# design_bci.net
KiCad netlist of a schematic drawn in EAGLE
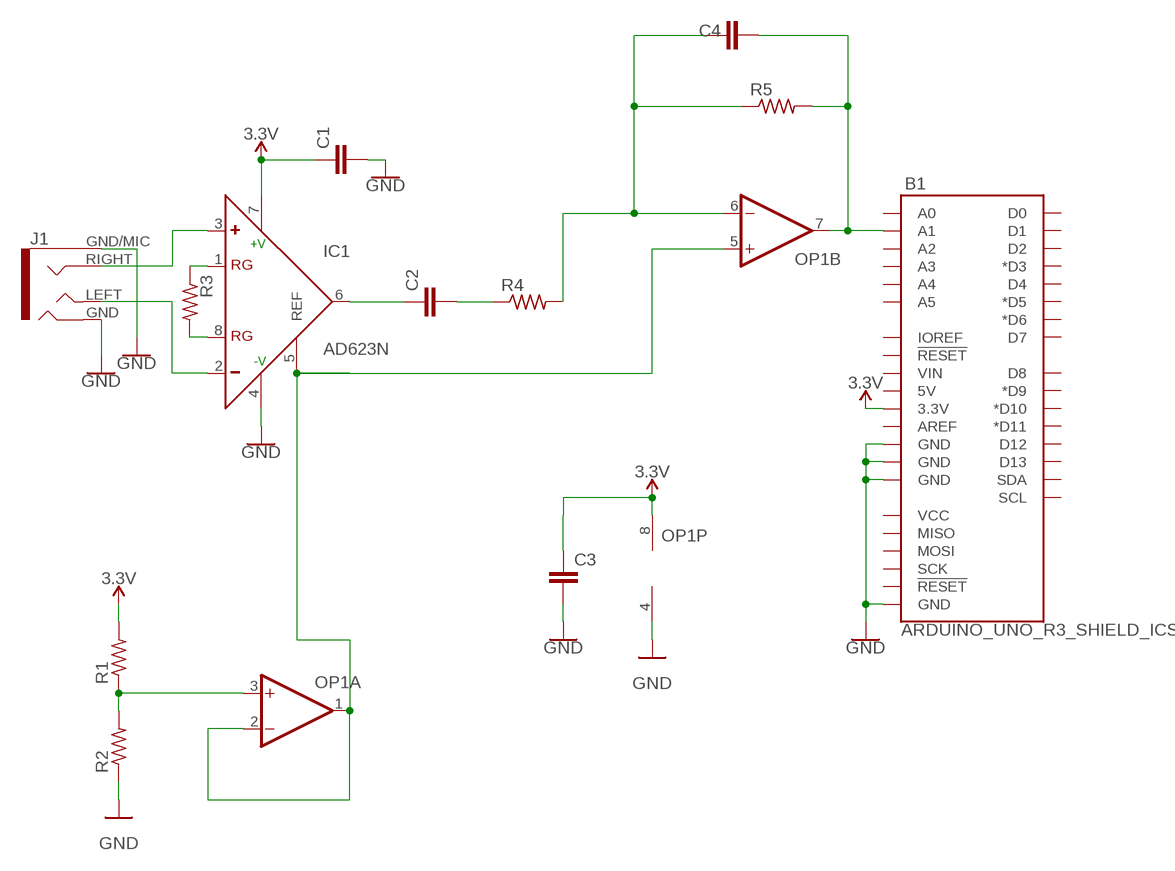
[diagram p0: schematic, sheet 1]

(export (version "E")
  (design (tool "Eeschema 10.0.6"))
  (components
    (comp (ref "B1")
      (value "ARDUINO_UNO_R3_SHIELD_ICSP")
      (footprint "eagle-import:UNO_R3_SHIELD_ICSP")
      (libsource (lib "eagle-import") (part "ARDUINO_UNO_R3_SHIELD_ICSP"))
    )
    (comp (ref "C1")
      (value "CAPACITOR0603")
      (footprint "eagle-import:C0603")
      (libsource (lib "eagle-import") (part "CAPACITOR0603"))
    )
    (comp (ref "C2")
      (value "CAPACITOR0603")
      (footprint "eagle-import:C0603")
      (libsource (lib "eagle-import") (part "CAPACITOR0603"))
    )
    (comp (ref "C3")
      (value "CAPACITOR0603")
      (footprint "eagle-import:C0603")
      (libsource (lib "eagle-import") (part "CAPACITOR0603"))
    )
    (comp (ref "C4")
      (value "CAPACITOR0603")
      (footprint "eagle-import:C0603")
      (libsource (lib "eagle-import") (part "CAPACITOR0603"))
    )
    (comp (ref "IC1")
      (value "AD623N")
      (footprint "eagle-import:DIL08")
      (fields (field (name "MF") "ALTERA CORPORATION") (field (name "MPN") "AD623ANZ"))
      (libsource (lib "eagle-import") (part "AD623N"))
    )
    (comp (ref "J1")
      (value "AUDIO_JACK_TRRSSMD_RA")
      (footprint "eagle-import:AUDIO_JACK_3.5MM_TRRS_SMD_RA")
      (libsource (lib "eagle-import") (part "AUDIO_JACK_TRRSSMD_RA"))
    )
    (comp (ref "OP1")
      (value "OP-DUALMCP6002R")
      (footprint "eagle-import:SO8")
      (fields (field (name "MF") "Microchip Technology") (field (name "MPN") "MCP6002T-I/SN"))
      (libsource (lib "eagle-import") (part "OP-DUALRMCP6002"))
    )
    (comp (ref "R1")
      (value "RESISTOR0603")
      (footprint "eagle-import:R0603")
      (libsource (lib "eagle-import") (part "RESISTOR0603"))
    )
    (comp (ref "R2")
      (value "RESISTOR0603")
      (footprint "eagle-import:R0603")
      (libsource (lib "eagle-import") (part "RESISTOR0603"))
    )
    (comp (ref "R3")
      (value "RESISTOR0603")
      (footprint "eagle-import:R0603")
      (libsource (lib "eagle-import") (part "RESISTOR0603"))
    )
    (comp (ref "R4")
      (value "RESISTOR0603")
      (footprint "eagle-import:R0603")
      (libsource (lib "eagle-import") (part "RESISTOR0603"))
    )
    (comp (ref "R5")
      (value "RESISTOR0603")
      (footprint "eagle-import:R0603")
      (libsource (lib "eagle-import") (part "RESISTOR0603"))
    )
  )
  (nets
    (net (code "1") (name "3.3V") (class "Default")
      (node (ref "B1") (pin "3.3V") (pinfunction "3.3V_3.3V") (pintype "bidirectional"))
      (node (ref "C1") (pin "1") (pinfunction "1_1") (pintype "passive"))
      (node (ref "C3") (pin "1") (pinfunction "1_1") (pintype "passive"))
      (node (ref "IC1") (pin "7") (pinfunction "+V_7") (pintype "power_in"))
      (node (ref "OP1") (pin "8") (pinfunction "V+_8") (pintype "power_in"))
      (node (ref "R1") (pin "2") (pinfunction "2_2") (pintype "passive"))
    )
    (net (code "2") (name "GND") (class "Default")
      (node (ref "B1") (pin "GND@0") (pinfunction "GND_GND@0") (pintype "bidirectional"))
      (node (ref "B1") (pin "GND@1") (pinfunction "GND_GND@1") (pintype "bidirectional"))
      (node (ref "B1") (pin "GND@2") (pinfunction "GND_GND@2") (pintype "bidirectional"))
      (node (ref "B1") (pin "GND_ICSP") (pinfunction "GND_GND_ICSP") (pintype "bidirectional"))
      (node (ref "C1") (pin "2") (pinfunction "2_2") (pintype "passive"))
      (node (ref "C3") (pin "2") (pinfunction "2_2") (pintype "passive"))
      (node (ref "IC1") (pin "4") (pinfunction "-V_4") (pintype "power_in"))
      (node (ref "J1") (pin "GND") (pinfunction "RING2_GND") (pintype "bidirectional"))
      (node (ref "J1") (pin "GND/MIC") (pinfunction "SLEEVE_GND/MIC") (pintype "bidirectional"))
      (node (ref "OP1") (pin "4") (pinfunction "V-_4") (pintype "power_in"))
      (node (ref "R2") (pin "1") (pinfunction "1_1") (pintype "passive"))
    )
    (net (code "3") (name "Net-(C2-Pad2)") (class "Default")
      (node (ref "C2") (pin "2") (pinfunction "2_2") (pintype "passive"))
      (node (ref "R4") (pin "1") (pinfunction "1_1") (pintype "passive"))
    )
    (net (code "4") (name "Net-(IC1-+)") (class "Default")
      (node (ref "IC1") (pin "3") (pinfunction "+_3") (pintype "input"))
      (node (ref "J1") (pin "RIGHT") (pinfunction "RING1_RIGHT") (pintype "bidirectional"))
    )
    (net (code "5") (name "Net-(IC1--)") (class "Default")
      (node (ref "IC1") (pin "2") (pinfunction "-_2") (pintype "input"))
      (node (ref "J1") (pin "LEFT") (pinfunction "TIP_LEFT") (pintype "bidirectional"))
    )
    (net (code "6") (name "Net-(IC1-OUT)") (class "Default")
      (node (ref "C2") (pin "1") (pinfunction "1_1") (pintype "passive"))
      (node (ref "IC1") (pin "6") (pinfunction "OUT_6") (pintype "output"))
    )
    (net (code "7") (name "Net-(IC1-REF)") (class "Default")
      (node (ref "IC1") (pin "5") (pinfunction "REF_5") (pintype "passive"))
      (node (ref "OP1") (pin "1") (pinfunction "OUT_1") (pintype "output"))
      (node (ref "OP1") (pin "2") (pinfunction "-IN_2") (pintype "input"))
      (node (ref "OP1") (pin "5") (pinfunction "+IN_5") (pintype "input"))
    )
    (net (code "8") (name "Net-(IC1-RG-Pad1)") (class "Default")
      (node (ref "IC1") (pin "1") (pinfunction "RG_1") (pintype "passive"))
      (node (ref "R3") (pin "1") (pinfunction "1_1") (pintype "passive"))
    )
    (net (code "9") (name "Net-(IC1-RG-Pad8)") (class "Default")
      (node (ref "IC1") (pin "8") (pinfunction "RG_8") (pintype "passive"))
      (node (ref "R3") (pin "2") (pinfunction "2_2") (pintype "passive"))
    )
    (net (code "10") (name "Net-(OP1A-+IN)") (class "Default")
      (node (ref "OP1") (pin "3") (pinfunction "+IN_3") (pintype "input"))
      (node (ref "R1") (pin "1") (pinfunction "1_1") (pintype "passive"))
      (node (ref "R2") (pin "2") (pinfunction "2_2") (pintype "passive"))
    )
    (net (code "11") (name "Net-(OP1B--IN)") (class "Default")
      (node (ref "C4") (pin "1") (pinfunction "1_1") (pintype "passive"))
      (node (ref "OP1") (pin "6") (pinfunction "-IN_6") (pintype "input"))
      (node (ref "R4") (pin "2") (pinfunction "2_2") (pintype "passive"))
      (node (ref "R5") (pin "1") (pinfunction "1_1") (pintype "passive"))
    )
    (net (code "12") (name "Net-(OP1B-OUT)") (class "Default")
      (node (ref "B1") (pin "A1") (pinfunction "A1_A1") (pintype "bidirectional"))
      (node (ref "C4") (pin "2") (pinfunction "2_2") (pintype "passive"))
      (node (ref "OP1") (pin "7") (pinfunction "OUT_7") (pintype "output"))
      (node (ref "R5") (pin "2") (pinfunction "2_2") (pintype "passive"))
    )
    (net (code "13") (name "unconnected-(B1-*D3-PadD3)") (class "Default")
      (node (ref "B1") (pin "D3") (pinfunction "*D3_D3") (pintype "bidirectional"))
    )
    (net (code "14") (name "unconnected-(B1-*D5-PadD5)") (class "Default")
      (node (ref "B1") (pin "D5") (pinfunction "*D5_D5") (pintype "bidirectional"))
    )
    (net (code "15") (name "unconnected-(B1-*D6-PadD6)") (class "Default")
      (node (ref "B1") (pin "D6") (pinfunction "*D6_D6") (pintype "bidirectional"))
    )
    (net (code "16") (name "unconnected-(B1-*D9-PadD9)") (class "Default")
      (node (ref "B1") (pin "D9") (pinfunction "*D9_D9") (pintype "bidirectional"))
    )
    (net (code "17") (name "unconnected-(B1-*D10-PadD10)") (class "Default")
      (node (ref "B1") (pin "D10") (pinfunction "*D10_D10") (pintype "bidirectional"))
    )
    (net (code "18") (name "unconnected-(B1-*D11-PadD11)") (class "Default")
      (node (ref "B1") (pin "D11") (pinfunction "*D11_D11") (pintype "bidirectional"))
    )
    (net (code "19") (name "unconnected-(B1-D0-PadRX)") (class "Default")
      (node (ref "B1") (pin "RX") (pinfunction "D0_RX") (pintype "bidirectional"))
    )
    (net (code "20") (name "unconnected-(B1-D1-PadTX)") (class "Default")
      (node (ref "B1") (pin "TX") (pinfunction "D1_TX") (pintype "bidirectional"))
    )
    (net (code "21") (name "unconnected-(B1-Pad5V)") (class "Default")
      (node (ref "B1") (pin "5V") (pinfunction "5V_5V") (pintype "bidirectional"))
    )
    (net (code "22") (name "unconnected-(B1-PadA0)") (class "Default")
      (node (ref "B1") (pin "A0") (pinfunction "A0_A0") (pintype "bidirectional"))
    )
    (net (code "23") (name "unconnected-(B1-PadA2)") (class "Default")
      (node (ref "B1") (pin "A2") (pinfunction "A2_A2") (pintype "bidirectional"))
    )
    (net (code "24") (name "unconnected-(B1-PadA3)") (class "Default")
      (node (ref "B1") (pin "A3") (pinfunction "A3_A3") (pintype "bidirectional"))
    )
    (net (code "25") (name "unconnected-(B1-PadA4)") (class "Default")
      (node (ref "B1") (pin "A4") (pinfunction "A4_A4") (pintype "bidirectional"))
    )
    (net (code "26") (name "unconnected-(B1-PadA5)") (class "Default")
      (node (ref "B1") (pin "A5") (pinfunction "A5_A5") (pintype "bidirectional"))
    )
    (net (code "27") (name "unconnected-(B1-PadAREF)") (class "Default")
      (node (ref "B1") (pin "AREF") (pinfunction "AREF_AREF") (pintype "bidirectional"))
    )
    (net (code "28") (name "unconnected-(B1-PadD2)") (class "Default")
      (node (ref "B1") (pin "D2") (pinfunction "D2_D2") (pintype "bidirectional"))
    )
    (net (code "29") (name "unconnected-(B1-PadD4)") (class "Default")
      (node (ref "B1") (pin "D4") (pinfunction "D4_D4") (pintype "bidirectional"))
    )
    (net (code "30") (name "unconnected-(B1-PadD7)") (class "Default")
      (node (ref "B1") (pin "D7") (pinfunction "D7_D7") (pintype "bidirectional"))
    )
    (net (code "31") (name "unconnected-(B1-PadD8)") (class "Default")
      (node (ref "B1") (pin "D8") (pinfunction "D8_D8") (pintype "bidirectional"))
    )
    (net (code "32") (name "unconnected-(B1-PadD12)") (class "Default")
      (node (ref "B1") (pin "D12") (pinfunction "D12_D12") (pintype "bidirectional"))
    )
    (net (code "33") (name "unconnected-(B1-PadD13)") (class "Default")
      (node (ref "B1") (pin "D13") (pinfunction "D13_D13") (pintype "bidirectional"))
    )
    (net (code "34") (name "unconnected-(B1-PadIOREF)") (class "Default")
      (node (ref "B1") (pin "IOREF") (pinfunction "IOREF_IOREF") (pintype "bidirectional"))
    )
    (net (code "35") (name "unconnected-(B1-PadMISO)") (class "Default")
      (node (ref "B1") (pin "MISO") (pinfunction "MISO_MISO") (pintype "bidirectional"))
    )
    (net (code "36") (name "unconnected-(B1-PadMOSI)") (class "Default")
      (node (ref "B1") (pin "MOSI") (pinfunction "MOSI_MOSI") (pintype "bidirectional"))
    )
    (net (code "37") (name "unconnected-(B1-PadSCK)") (class "Default")
      (node (ref "B1") (pin "SCK") (pinfunction "SCK_SCK") (pintype "bidirectional"))
    )
    (net (code "38") (name "unconnected-(B1-PadSCL)") (class "Default")
      (node (ref "B1") (pin "SCL") (pinfunction "SCL_SCL") (pintype "bidirectional"))
    )
    (net (code "39") (name "unconnected-(B1-PadSDA)") (class "Default")
      (node (ref "B1") (pin "SDA") (pinfunction "SDA_SDA") (pintype "bidirectional"))
    )
    (net (code "40") (name "unconnected-(B1-PadVIN)") (class "Default")
      (node (ref "B1") (pin "VIN") (pinfunction "VIN_VIN") (pintype "bidirectional"))
    )
    (net (code "41") (name "unconnected-(B1-VCC-Pad5V_ICSP)") (class "Default")
      (node (ref "B1") (pin "5V_ICSP") (pinfunction "VCC_5V_ICSP") (pintype "bidirectional"))
    )
    (net (code "42") (name "unconnected-(B1-~{RESET}-PadRES)") (class "Default")
      (node (ref "B1") (pin "RES") (pinfunction "~{RESET}_RES") (pintype "bidirectional"))
    )
    (net (code "43") (name "unconnected-(B1-~{RESET}-PadRST_ICSP)") (class "Default")
      (node (ref "B1") (pin "RST_ICSP") (pinfunction "~{RESET}_RST_ICSP") (pintype "bidirectional"))
    )
  )
)
